# breakout.net
KiCad netlist of a schematic drawn in EAGLE
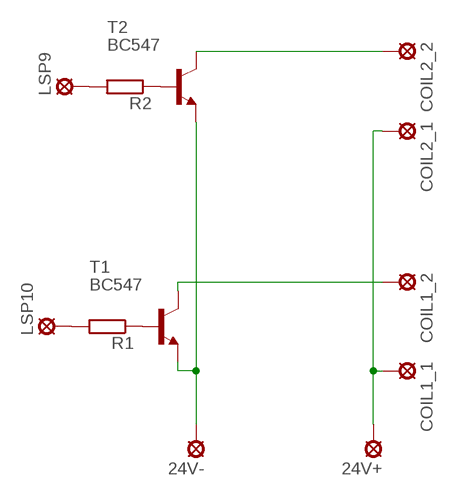
[diagram p0: schematic, sheet 1]

(export (version "E")
  (design (tool "Eeschema 10.0.6"))
  (components
    (comp (ref "24V+")
      (value "LSP10")
      (footprint "eagle-import:LSP10")
      (libsource (lib "eagle-import") (part "LSP10"))
    )
    (comp (ref "24V-")
      (value "LSP10")
      (footprint "eagle-import:LSP10")
      (libsource (lib "eagle-import") (part "LSP10"))
    )
    (comp (ref "COIL1_1")
      (value "LSP10")
      (footprint "eagle-import:LSP10")
      (libsource (lib "eagle-import") (part "LSP10"))
    )
    (comp (ref "COIL1_2")
      (value "LSP10")
      (footprint "eagle-import:LSP10")
      (libsource (lib "eagle-import") (part "LSP10"))
    )
    (comp (ref "COIL2_1")
      (value "LSP10")
      (footprint "eagle-import:LSP10")
      (libsource (lib "eagle-import") (part "LSP10"))
    )
    (comp (ref "COIL2_2")
      (value "LSP10")
      (footprint "eagle-import:LSP10")
      (libsource (lib "eagle-import") (part "LSP10"))
    )
    (comp (ref "LSP9")
      (value "LSP10")
      (footprint "eagle-import:LSP10")
      (libsource (lib "eagle-import") (part "LSP10"))
    )
    (comp (ref "LSP10")
      (value "LSP10")
      (footprint "eagle-import:LSP10")
      (libsource (lib "eagle-import") (part "LSP10"))
    )
    (comp (ref "R1")
      (value "R-EU_V235/17")
      (footprint "eagle-import:V235_17")
      (libsource (lib "eagle-import") (part "R-EU_V235/17"))
    )
    (comp (ref "R2")
      (value "R-EU_V235/17")
      (footprint "eagle-import:V235_17")
      (libsource (lib "eagle-import") (part "R-EU_V235/17"))
    )
    (comp (ref "T1")
      (value "BC547")
      (footprint "eagle-import:TO92")
      (libsource (lib "eagle-import") (part "BC547"))
    )
    (comp (ref "T2")
      (value "BC547")
      (footprint "eagle-import:TO92")
      (libsource (lib "eagle-import") (part "BC547"))
    )
  )
  (nets
    (net (code "1") (name "Net-(24V+-PadMP)") (class "Default")
      (node (ref "24V+") (pin "MP") (pinfunction "MP_MP") (pintype "passive"))
      (node (ref "COIL1_1") (pin "MP") (pinfunction "MP_MP") (pintype "passive"))
      (node (ref "COIL2_1") (pin "MP") (pinfunction "MP_MP") (pintype "passive"))
    )
    (net (code "2") (name "Net-(LSP9-PadMP)") (class "Default")
      (node (ref "LSP9") (pin "MP") (pinfunction "MP_MP") (pintype "passive"))
      (node (ref "R2") (pin "2") (pinfunction "2_2") (pintype "passive"))
    )
    (net (code "3") (name "Net-(LSP10-PadMP)") (class "Default")
      (node (ref "LSP10") (pin "MP") (pinfunction "MP_MP") (pintype "passive"))
      (node (ref "R1") (pin "2") (pinfunction "2_2") (pintype "passive"))
    )
    (net (code "4") (name "Net-(T1-B)") (class "Default")
      (node (ref "R1") (pin "1") (pinfunction "1_1") (pintype "passive"))
      (node (ref "T1") (pin "2") (pinfunction "B_2") (pintype "passive"))
    )
    (net (code "5") (name "Net-(T1-C)") (class "Default")
      (node (ref "COIL1_2") (pin "MP") (pinfunction "MP_MP") (pintype "passive"))
      (node (ref "T1") (pin "3") (pinfunction "C_3") (pintype "passive"))
    )
    (net (code "6") (name "Net-(T1-E)") (class "Default")
      (node (ref "24V-") (pin "MP") (pinfunction "MP_MP") (pintype "passive"))
      (node (ref "T1") (pin "1") (pinfunction "E_1") (pintype "passive"))
      (node (ref "T2") (pin "1") (pinfunction "E_1") (pintype "passive"))
    )
    (net (code "7") (name "Net-(T2-B)") (class "Default")
      (node (ref "R2") (pin "1") (pinfunction "1_1") (pintype "passive"))
      (node (ref "T2") (pin "2") (pinfunction "B_2") (pintype "passive"))
    )
    (net (code "8") (name "Net-(T2-C)") (class "Default")
      (node (ref "COIL2_2") (pin "MP") (pinfunction "MP_MP") (pintype "passive"))
      (node (ref "T2") (pin "3") (pinfunction "C_3") (pintype "passive"))
    )
  )
)
